# KeyBoard.net
KiCad netlist of a schematic drawn in EasyEDA Pro
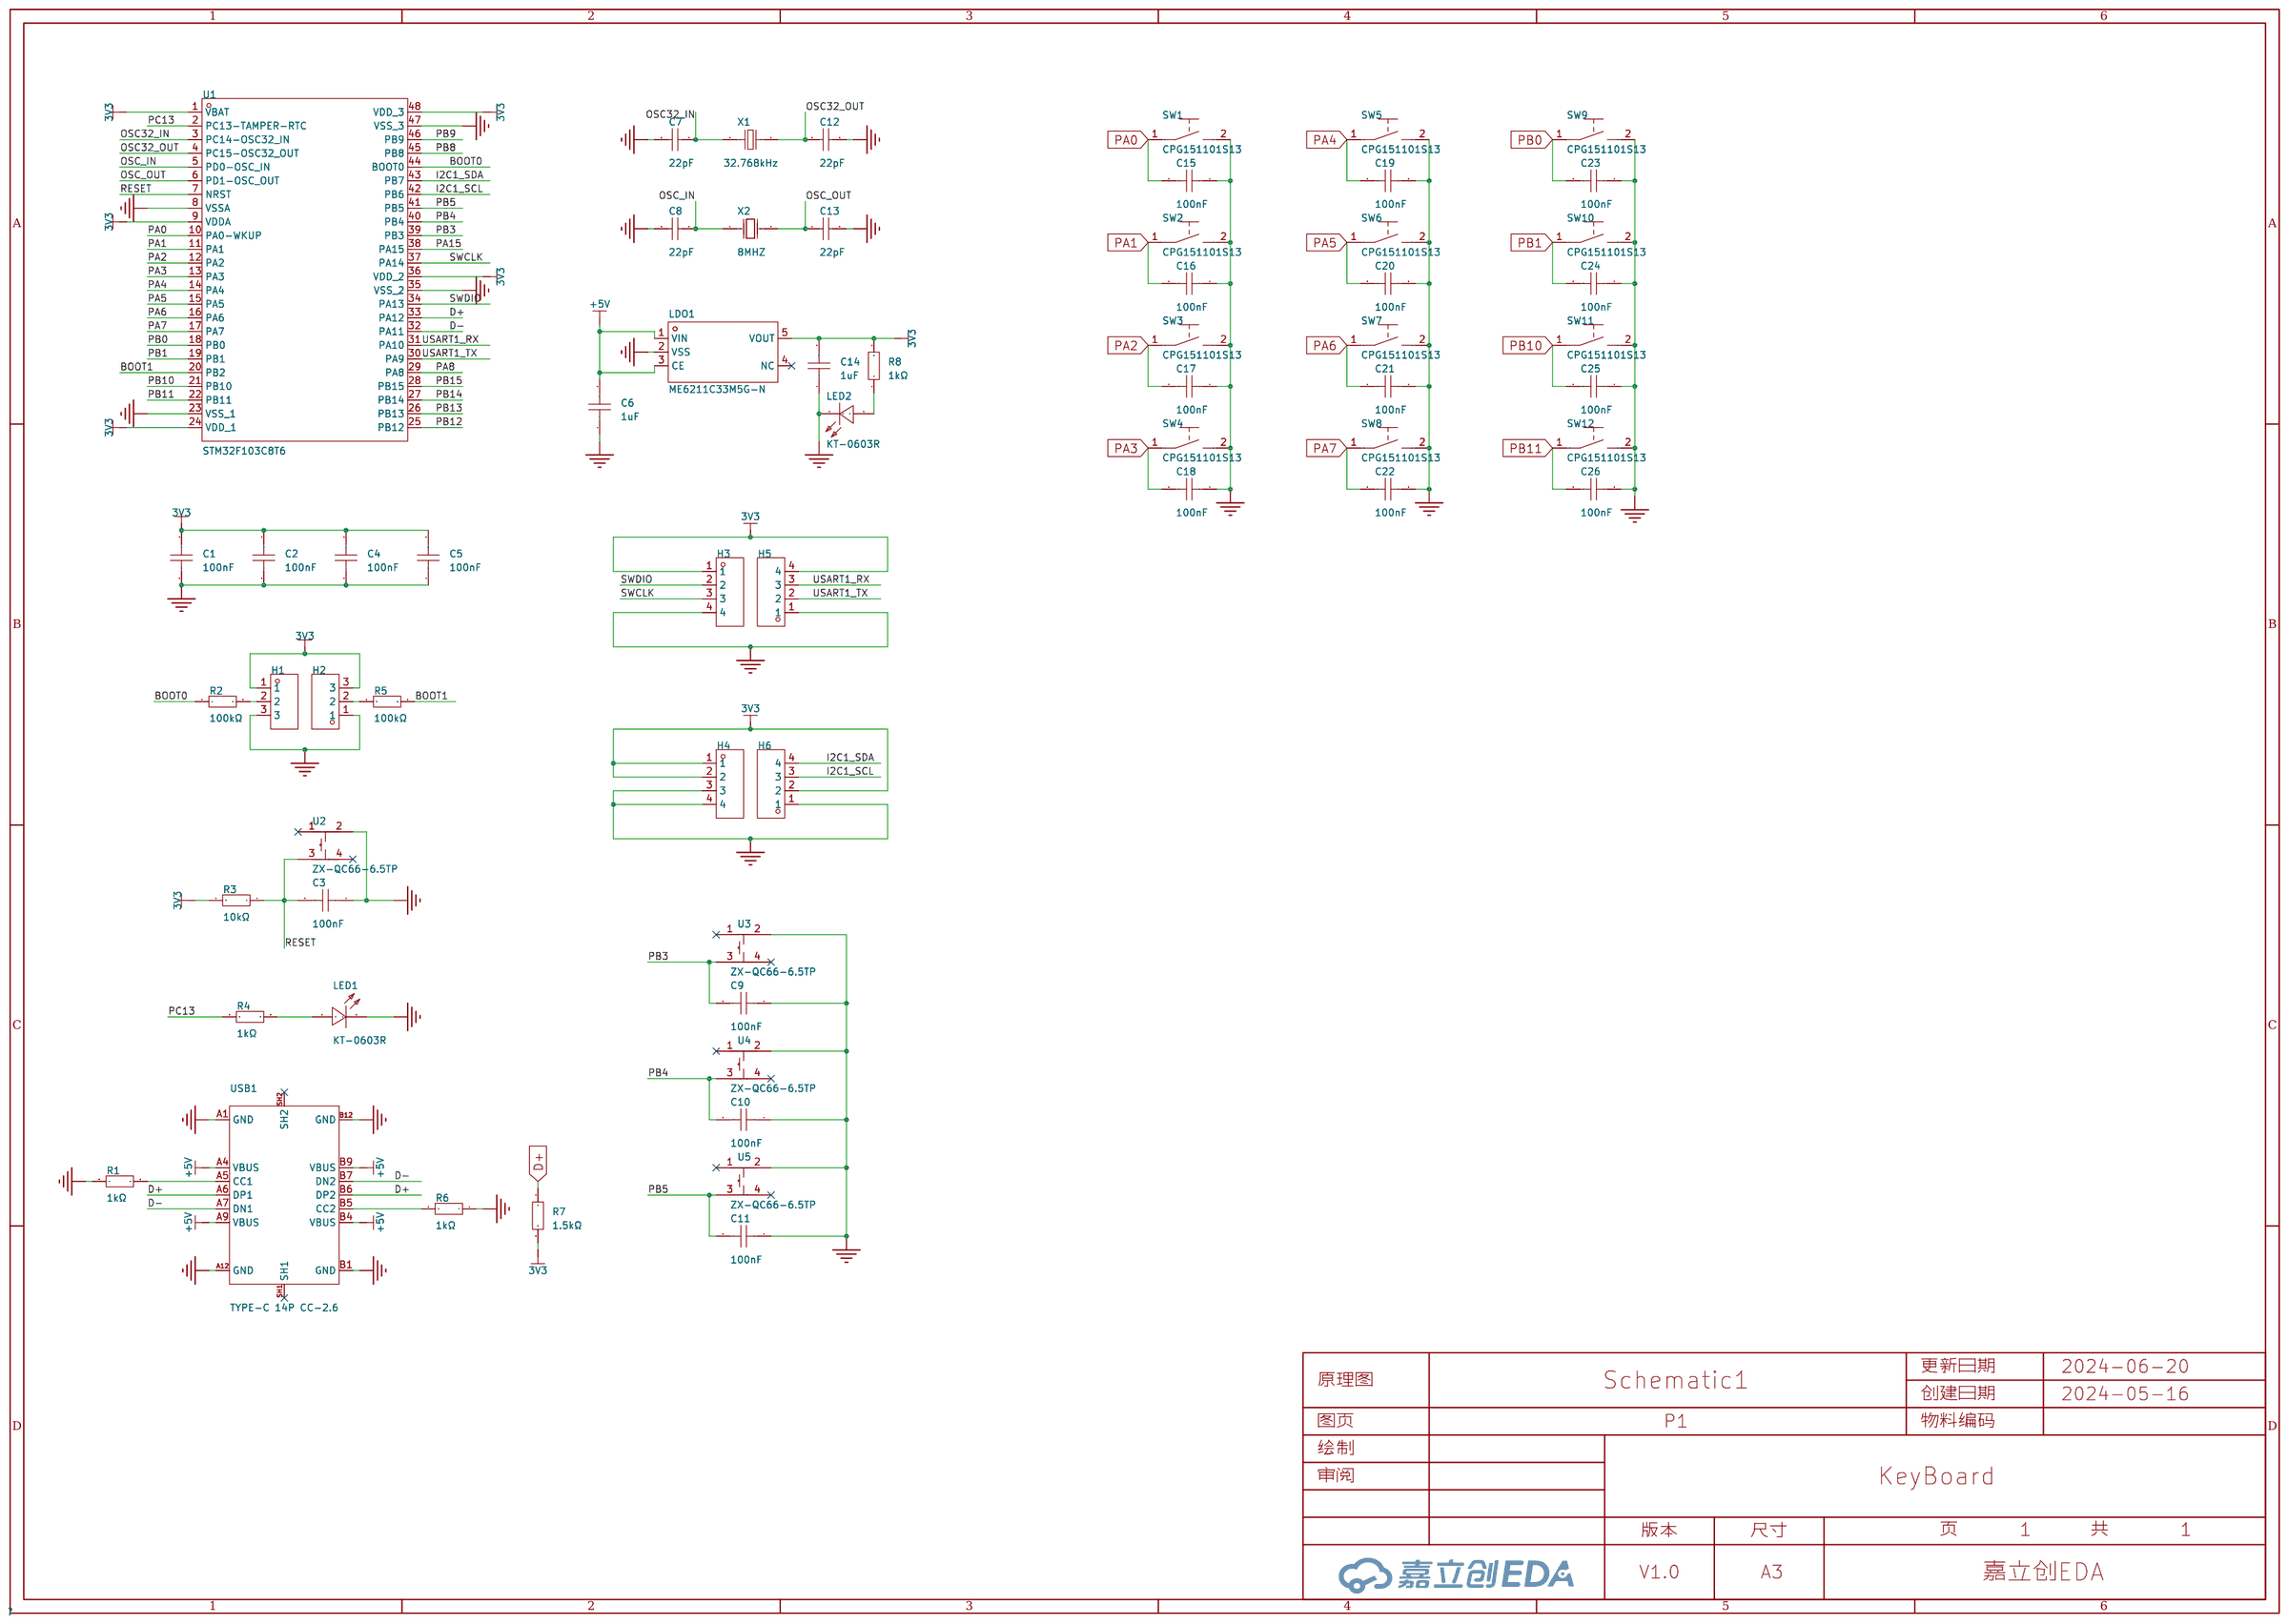
[diagram p0: schematic sheet]

(export (version "E")
  (design (tool "Eeschema 10.0.6"))
  (components
    (comp (ref "C1")
      (value "100nF")
      (footprint "easyedapro:C0603")
      (description "容值:100nF;精度:±10%;额定电压:50V;材质(温度系数):X7R;")
      (fields
        (field (name "Manufacturer Part") "CC0603KRX7R9BB104")
        (field (name "Manufacturer") "YAGEO(国巨)")
      )
      (libsource (lib "easyedapro") (part "CC0603KRX7R9BB104"))
    )
    (comp (ref "C2")
      (value "100nF")
      (footprint "easyedapro:C0603")
      (description "容值:100nF;精度:±10%;额定电压:50V;材质(温度系数):X7R;")
      (fields
        (field (name "Manufacturer Part") "CC0603KRX7R9BB104")
        (field (name "Manufacturer") "YAGEO(国巨)")
      )
      (libsource (lib "easyedapro") (part "CC0603KRX7R9BB104"))
    )
    (comp (ref "C3")
      (value "100nF")
      (footprint "easyedapro:C0603")
      (description "容值:100nF;精度:±10%;额定电压:50V;材质(温度系数):X7R;")
      (fields
        (field (name "Manufacturer Part") "CC0603KRX7R9BB104")
        (field (name "Manufacturer") "YAGEO(国巨)")
      )
      (libsource (lib "easyedapro") (part "CC0603KRX7R9BB104"))
    )
    (comp (ref "C4")
      (value "100nF")
      (footprint "easyedapro:C0603")
      (description "容值:100nF;精度:±10%;额定电压:50V;材质(温度系数):X7R;")
      (fields
        (field (name "Manufacturer Part") "CC0603KRX7R9BB104")
        (field (name "Manufacturer") "YAGEO(国巨)")
      )
      (libsource (lib "easyedapro") (part "CC0603KRX7R9BB104"))
    )
    (comp (ref "C5")
      (value "100nF")
      (footprint "easyedapro:C0603")
      (description "容值:100nF;精度:±10%;额定电压:50V;材质(温度系数):X7R;")
      (fields
        (field (name "Manufacturer Part") "CC0603KRX7R9BB104")
        (field (name "Manufacturer") "YAGEO(国巨)")
      )
      (libsource (lib "easyedapro") (part "CC0603KRX7R9BB104"))
    )
    (comp (ref "C6")
      (value "1uF")
      (footprint "easyedapro:C0603")
      (description "容值:1uF;精度:±10%;额定电压:50V;材质(温度系数):X5R;")
      (fields
        (field (name "Manufacturer Part") "CL10A105KB8NNNC")
        (field (name "Manufacturer") "SAMSUNG(三星)")
      )
      (libsource (lib "easyedapro") (part "CL10A105KB8NNNC"))
    )
    (comp (ref "C7")
      (value "22pF")
      (footprint "easyedapro:C0603")
      (description "容值:22pF;精度:±5%;额定电压:50V;材质(温度系数):C0G;")
      (fields
        (field (name "Manufacturer Part") "CL10C220JB8NNNC")
        (field (name "Manufacturer") "SAMSUNG(三星)")
      )
      (libsource (lib "easyedapro") (part "CL10C220JB8NNNC"))
    )
    (comp (ref "C8")
      (value "22pF")
      (footprint "easyedapro:C0603")
      (description "容值:22pF;精度:±5%;额定电压:50V;材质(温度系数):C0G;")
      (fields
        (field (name "Manufacturer Part") "CL10C220JB8NNNC")
        (field (name "Manufacturer") "SAMSUNG(三星)")
      )
      (libsource (lib "easyedapro") (part "CL10C220JB8NNNC"))
    )
    (comp (ref "C9")
      (value "100nF")
      (footprint "easyedapro:C0603")
      (description "容值:100nF;精度:±10%;额定电压:50V;材质(温度系数):X7R;")
      (fields
        (field (name "Manufacturer Part") "CC0603KRX7R9BB104")
        (field (name "Manufacturer") "YAGEO(国巨)")
      )
      (libsource (lib "easyedapro") (part "CC0603KRX7R9BB104"))
    )
    (comp (ref "C10")
      (value "100nF")
      (footprint "easyedapro:C0603")
      (description "容值:100nF;精度:±10%;额定电压:50V;材质(温度系数):X7R;")
      (fields
        (field (name "Manufacturer Part") "CC0603KRX7R9BB104")
        (field (name "Manufacturer") "YAGEO(国巨)")
      )
      (libsource (lib "easyedapro") (part "CC0603KRX7R9BB104"))
    )
    (comp (ref "C11")
      (value "100nF")
      (footprint "easyedapro:C0603")
      (description "容值:100nF;精度:±10%;额定电压:50V;材质(温度系数):X7R;")
      (fields
        (field (name "Manufacturer Part") "CC0603KRX7R9BB104")
        (field (name "Manufacturer") "YAGEO(国巨)")
      )
      (libsource (lib "easyedapro") (part "CC0603KRX7R9BB104"))
    )
    (comp (ref "C12")
      (value "22pF")
      (footprint "easyedapro:C0603")
      (description "容值:22pF;精度:±5%;额定电压:50V;材质(温度系数):C0G;")
      (fields
        (field (name "Manufacturer Part") "CL10C220JB8NNNC")
        (field (name "Manufacturer") "SAMSUNG(三星)")
      )
      (libsource (lib "easyedapro") (part "CL10C220JB8NNNC"))
    )
    (comp (ref "C13")
      (value "22pF")
      (footprint "easyedapro:C0603")
      (description "容值:22pF;精度:±5%;额定电压:50V;材质(温度系数):C0G;")
      (fields
        (field (name "Manufacturer Part") "CL10C220JB8NNNC")
        (field (name "Manufacturer") "SAMSUNG(三星)")
      )
      (libsource (lib "easyedapro") (part "CL10C220JB8NNNC"))
    )
    (comp (ref "C14")
      (value "1uF")
      (footprint "easyedapro:C0603")
      (description "容值:1uF;精度:±10%;额定电压:50V;材质(温度系数):X5R;")
      (fields
        (field (name "Manufacturer Part") "CL10A105KB8NNNC")
        (field (name "Manufacturer") "SAMSUNG(三星)")
      )
      (libsource (lib "easyedapro") (part "CL10A105KB8NNNC"))
    )
    (comp (ref "C15")
      (value "100nF")
      (footprint "easyedapro:C0603")
      (description "容值:100nF;精度:±10%;额定电压:50V;材质(温度系数):X7R;")
      (fields
        (field (name "Manufacturer Part") "CC0603KRX7R9BB104")
        (field (name "Manufacturer") "YAGEO(国巨)")
      )
      (libsource (lib "easyedapro") (part "CC0603KRX7R9BB104"))
    )
    (comp (ref "C16")
      (value "100nF")
      (footprint "easyedapro:C0603")
      (description "容值:100nF;精度:±10%;额定电压:50V;材质(温度系数):X7R;")
      (fields
        (field (name "Manufacturer Part") "CC0603KRX7R9BB104")
        (field (name "Manufacturer") "YAGEO(国巨)")
      )
      (libsource (lib "easyedapro") (part "CC0603KRX7R9BB104"))
    )
    (comp (ref "C17")
      (value "100nF")
      (footprint "easyedapro:C0603")
      (description "容值:100nF;精度:±10%;额定电压:50V;材质(温度系数):X7R;")
      (fields
        (field (name "Manufacturer Part") "CC0603KRX7R9BB104")
        (field (name "Manufacturer") "YAGEO(国巨)")
      )
      (libsource (lib "easyedapro") (part "CC0603KRX7R9BB104"))
    )
    (comp (ref "C18")
      (value "100nF")
      (footprint "easyedapro:C0603")
      (description "容值:100nF;精度:±10%;额定电压:50V;材质(温度系数):X7R;")
      (fields
        (field (name "Manufacturer Part") "CC0603KRX7R9BB104")
        (field (name "Manufacturer") "YAGEO(国巨)")
      )
      (libsource (lib "easyedapro") (part "CC0603KRX7R9BB104"))
    )
    (comp (ref "C19")
      (value "100nF")
      (footprint "easyedapro:C0603")
      (description "容值:100nF;精度:±10%;额定电压:50V;材质(温度系数):X7R;")
      (fields
        (field (name "Manufacturer Part") "CC0603KRX7R9BB104")
        (field (name "Manufacturer") "YAGEO(国巨)")
      )
      (libsource (lib "easyedapro") (part "CC0603KRX7R9BB104"))
    )
    (comp (ref "C20")
      (value "100nF")
      (footprint "easyedapro:C0603")
      (description "容值:100nF;精度:±10%;额定电压:50V;材质(温度系数):X7R;")
      (fields
        (field (name "Manufacturer Part") "CC0603KRX7R9BB104")
        (field (name "Manufacturer") "YAGEO(国巨)")
      )
      (libsource (lib "easyedapro") (part "CC0603KRX7R9BB104"))
    )
    (comp (ref "C21")
      (value "100nF")
      (footprint "easyedapro:C0603")
      (description "容值:100nF;精度:±10%;额定电压:50V;材质(温度系数):X7R;")
      (fields
        (field (name "Manufacturer Part") "CC0603KRX7R9BB104")
        (field (name "Manufacturer") "YAGEO(国巨)")
      )
      (libsource (lib "easyedapro") (part "CC0603KRX7R9BB104"))
    )
    (comp (ref "C22")
      (value "100nF")
      (footprint "easyedapro:C0603")
      (description "容值:100nF;精度:±10%;额定电压:50V;材质(温度系数):X7R;")
      (fields
        (field (name "Manufacturer Part") "CC0603KRX7R9BB104")
        (field (name "Manufacturer") "YAGEO(国巨)")
      )
      (libsource (lib "easyedapro") (part "CC0603KRX7R9BB104"))
    )
    (comp (ref "C23")
      (value "100nF")
      (footprint "easyedapro:C0603")
      (description "容值:100nF;精度:±10%;额定电压:50V;材质(温度系数):X7R;")
      (fields
        (field (name "Manufacturer Part") "CC0603KRX7R9BB104")
        (field (name "Manufacturer") "YAGEO(国巨)")
      )
      (libsource (lib "easyedapro") (part "CC0603KRX7R9BB104"))
    )
    (comp (ref "C24")
      (value "100nF")
      (footprint "easyedapro:C0603")
      (description "容值:100nF;精度:±10%;额定电压:50V;材质(温度系数):X7R;")
      (fields
        (field (name "Manufacturer Part") "CC0603KRX7R9BB104")
        (field (name "Manufacturer") "YAGEO(国巨)")
      )
      (libsource (lib "easyedapro") (part "CC0603KRX7R9BB104"))
    )
    (comp (ref "C25")
      (value "100nF")
      (footprint "easyedapro:C0603")
      (description "容值:100nF;精度:±10%;额定电压:50V;材质(温度系数):X7R;")
      (fields
        (field (name "Manufacturer Part") "CC0603KRX7R9BB104")
        (field (name "Manufacturer") "YAGEO(国巨)")
      )
      (libsource (lib "easyedapro") (part "CC0603KRX7R9BB104"))
    )
    (comp (ref "C26")
      (value "100nF")
      (footprint "easyedapro:C0603")
      (description "容值:100nF;精度:±10%;额定电压:50V;材质(温度系数):X7R;")
      (fields
        (field (name "Manufacturer Part") "CC0603KRX7R9BB104")
        (field (name "Manufacturer") "YAGEO(国巨)")
      )
      (libsource (lib "easyedapro") (part "CC0603KRX7R9BB104"))
    )
    (comp (ref "H1")
      (value "~")
      (footprint "easyedapro:HDR-TH_3P-P2.54-V-F")
      (libsource (lib "easyedapro") (part "PM254V-11-03-H85"))
    )
    (comp (ref "H2")
      (value "~")
      (footprint "easyedapro:HDR-TH_3P-P2.54-V-F")
      (libsource (lib "easyedapro") (part "PM254V-11-03-H85"))
    )
    (comp (ref "H3")
      (value "~")
      (footprint "easyedapro:HDR-TH_4P-P2.54-V-F")
      (libsource (lib "easyedapro") (part "2.54-1*4P母"))
    )
    (comp (ref "H4")
      (value "~")
      (footprint "easyedapro:HDR-TH_4P-P2.54-V-F")
      (libsource (lib "easyedapro") (part "2.54-1*4P母"))
    )
    (comp (ref "H5")
      (value "~")
      (footprint "easyedapro:HDR-TH_4P-P2.54-V-F")
      (libsource (lib "easyedapro") (part "2.54-1*4P母"))
    )
    (comp (ref "H6")
      (value "~")
      (footprint "easyedapro:HDR-TH_4P-P2.54-V-F")
      (libsource (lib "easyedapro") (part "2.54-1*4P母"))
    )
    (comp (ref "LDO1")
      (value "ME6211C33M5G-N")
      (footprint "easyedapro:SOT-23-5_L3.0-W1.7-P0.95-LS2.8-BL")
      (description "输出类型:固定;最大输入电压:6V;输出电压:3.3V;最大输出电流:500mA;电源纹波抑制比(PSRR):70dB;输出极性:正极;")
      (fields (field (name "Manufacturer") "MICRONE(南京微盟)"))
      (libsource (lib "easyedapro") (part "ME6211C33M5G-N"))
    )
    (comp (ref "LED1")
      (value "KT-0603R")
      (footprint "easyedapro:LED0603-RD")
      (description "发光颜色:红色;功率:-;正向电流:-;主波长:-;二极管配置:-;透镜颜色:-;色温:-;发光角度:-;载带方式:-;工作温度:-40°C~+85°C;")
      (fields (field (name "Manufacturer") "KENTO"))
      (libsource (lib "easyedapro") (part "KT-0603R"))
    )
    (comp (ref "LED2")
      (value "KT-0603R")
      (footprint "easyedapro:LED0603-RD")
      (description "发光颜色:红色;功率:-;正向电流:-;主波长:-;二极管配置:-;透镜颜色:-;色温:-;发光角度:-;载带方式:-;工作温度:-40°C~+85°C;")
      (fields (field (name "Manufacturer") "KENTO"))
      (libsource (lib "easyedapro") (part "KT-0603R"))
    )
    (comp (ref "R1")
      (value "1kΩ")
      (footprint "easyedapro:R0603")
      (description "电阻类型:厚膜电阻;阻值:10kΩ;精度:±1%;功率:100mW;最大工作电压:75V;温度系数:±100ppm/°C;")
      (fields
        (field (name "Manufacturer Part") "0603WAF1002T5E")
        (field (name "Manufacturer") "UNI-ROYAL(厚声)")
      )
      (libsource (lib "easyedapro") (part "0603WAF1002T5E"))
    )
    (comp (ref "R2")
      (value "100kΩ")
      (footprint "easyedapro:R0603")
      (description "电阻类型:厚膜电阻;阻值:100kΩ;精度:±1%;功率:100mW;最大工作电压:75V;温度系数:±100ppm/°C;")
      (fields
        (field (name "Manufacturer Part") "0603WAF1003T5E")
        (field (name "Manufacturer") "UNI-ROYAL(厚声)")
      )
      (libsource (lib "easyedapro") (part "0603WAF1003T5E"))
    )
    (comp (ref "R3")
      (value "10kΩ")
      (footprint "easyedapro:R0603")
      (description "电阻类型:厚膜电阻;阻值:10kΩ;精度:±1%;功率:100mW;最大工作电压:75V;温度系数:±100ppm/°C;")
      (fields
        (field (name "Manufacturer Part") "0603WAF1002T5E")
        (field (name "Manufacturer") "UNI-ROYAL(厚声)")
      )
      (libsource (lib "easyedapro") (part "0603WAF1002T5E"))
    )
    (comp (ref "R4")
      (value "1kΩ")
      (footprint "easyedapro:R0603")
      (description "电阻类型:厚膜电阻;阻值:1kΩ;精度:±1%;功率:100mW;最大工作电压:75V;温度系数:±100ppm/°C;")
      (fields
        (field (name "Manufacturer Part") "0603WAF1001T5E")
        (field (name "Manufacturer") "UNI-ROYAL(厚声)")
      )
      (libsource (lib "easyedapro") (part "0603WAF1001T5E"))
    )
    (comp (ref "R5")
      (value "100kΩ")
      (footprint "easyedapro:R0603")
      (description "电阻类型:厚膜电阻;阻值:100kΩ;精度:±1%;功率:100mW;最大工作电压:75V;温度系数:±100ppm/°C;")
      (fields
        (field (name "Manufacturer Part") "0603WAF1003T5E")
        (field (name "Manufacturer") "UNI-ROYAL(厚声)")
      )
      (libsource (lib "easyedapro") (part "0603WAF1003T5E"))
    )
    (comp (ref "R6")
      (value "1kΩ")
      (footprint "easyedapro:R0603")
      (description "电阻类型:厚膜电阻;阻值:10kΩ;精度:±1%;功率:100mW;最大工作电压:75V;温度系数:±100ppm/°C;")
      (fields
        (field (name "Manufacturer Part") "0603WAF1002T5E")
        (field (name "Manufacturer") "UNI-ROYAL(厚声)")
      )
      (libsource (lib "easyedapro") (part "0603WAF1002T5E"))
    )
    (comp (ref "R7")
      (value "1.5kΩ")
      (footprint "easyedapro:R0603")
      (description "电阻类型:厚膜电阻;阻值:1.5kΩ;精度:±1%;功率:100mW;最大工作电压:75V;温度系数:±100ppm/°C;")
      (fields
        (field (name "Manufacturer Part") "0603WAF1501T5E")
        (field (name "Manufacturer") "UNI-ROYAL(厚声)")
      )
      (libsource (lib "easyedapro") (part "0603WAF1501T5E"))
    )
    (comp (ref "R8")
      (value "1kΩ")
      (footprint "easyedapro:R0603")
      (description "电阻类型:厚膜电阻;阻值:1kΩ;精度:±1%;功率:100mW;最大工作电压:75V;温度系数:±100ppm/°C;")
      (fields
        (field (name "Manufacturer Part") "0603WAF1001T5E")
        (field (name "Manufacturer") "UNI-ROYAL(厚声)")
      )
      (libsource (lib "easyedapro") (part "0603WAF1001T5E"))
    )
    (comp (ref "SW1")
      (value "CPG151101S13")
      (footprint "easyedapro:KEY-TH_CPG1511F01S0X")
      (description "轴类型:青轴;工作电压:2V~12V;针脚数:2;操作力:50gf@±10gf;")
      (fields (field (name "Manufacturer") "Kailh(凯华)"))
      (libsource (lib "easyedapro") (part "CPG151101S13"))
    )
    (comp (ref "SW2")
      (value "CPG151101S13")
      (footprint "easyedapro:KEY-TH_CPG1511F01S0X")
      (description "轴类型:青轴;工作电压:2V~12V;针脚数:2;操作力:50gf@±10gf;")
      (fields (field (name "Manufacturer") "Kailh(凯华)"))
      (libsource (lib "easyedapro") (part "CPG151101S13"))
    )
    (comp (ref "SW3")
      (value "CPG151101S13")
      (footprint "easyedapro:KEY-TH_CPG1511F01S0X")
      (description "轴类型:青轴;工作电压:2V~12V;针脚数:2;操作力:50gf@±10gf;")
      (fields (field (name "Manufacturer") "Kailh(凯华)"))
      (libsource (lib "easyedapro") (part "CPG151101S13"))
    )
    (comp (ref "SW4")
      (value "CPG151101S13")
      (footprint "easyedapro:KEY-TH_CPG1511F01S0X")
      (description "轴类型:青轴;工作电压:2V~12V;针脚数:2;操作力:50gf@±10gf;")
      (fields (field (name "Manufacturer") "Kailh(凯华)"))
      (libsource (lib "easyedapro") (part "CPG151101S13"))
    )
    (comp (ref "SW5")
      (value "CPG151101S13")
      (footprint "easyedapro:KEY-TH_CPG1511F01S0X")
      (description "轴类型:青轴;工作电压:2V~12V;针脚数:2;操作力:50gf@±10gf;")
      (fields (field (name "Manufacturer") "Kailh(凯华)"))
      (libsource (lib "easyedapro") (part "CPG151101S13"))
    )
    (comp (ref "SW6")
      (value "CPG151101S13")
      (footprint "easyedapro:KEY-TH_CPG1511F01S0X")
      (description "轴类型:青轴;工作电压:2V~12V;针脚数:2;操作力:50gf@±10gf;")
      (fields (field (name "Manufacturer") "Kailh(凯华)"))
      (libsource (lib "easyedapro") (part "CPG151101S13"))
    )
    (comp (ref "SW7")
      (value "CPG151101S13")
      (footprint "easyedapro:KEY-TH_CPG1511F01S0X")
      (description "轴类型:青轴;工作电压:2V~12V;针脚数:2;操作力:50gf@±10gf;")
      (fields (field (name "Manufacturer") "Kailh(凯华)"))
      (libsource (lib "easyedapro") (part "CPG151101S13"))
    )
    (comp (ref "SW8")
      (value "CPG151101S13")
      (footprint "easyedapro:KEY-TH_CPG1511F01S0X")
      (description "轴类型:青轴;工作电压:2V~12V;针脚数:2;操作力:50gf@±10gf;")
      (fields (field (name "Manufacturer") "Kailh(凯华)"))
      (libsource (lib "easyedapro") (part "CPG151101S13"))
    )
    (comp (ref "SW9")
      (value "CPG151101S13")
      (footprint "easyedapro:KEY-TH_CPG1511F01S0X")
      (description "轴类型:青轴;工作电压:2V~12V;针脚数:2;操作力:50gf@±10gf;")
      (fields (field (name "Manufacturer") "Kailh(凯华)"))
      (libsource (lib "easyedapro") (part "CPG151101S13"))
    )
    (comp (ref "SW10")
      (value "CPG151101S13")
      (footprint "easyedapro:KEY-TH_CPG1511F01S0X")
      (description "轴类型:青轴;工作电压:2V~12V;针脚数:2;操作力:50gf@±10gf;")
      (fields (field (name "Manufacturer") "Kailh(凯华)"))
      (libsource (lib "easyedapro") (part "CPG151101S13"))
    )
    (comp (ref "SW11")
      (value "CPG151101S13")
      (footprint "easyedapro:KEY-TH_CPG1511F01S0X")
      (description "轴类型:青轴;工作电压:2V~12V;针脚数:2;操作力:50gf@±10gf;")
      (fields (field (name "Manufacturer") "Kailh(凯华)"))
      (libsource (lib "easyedapro") (part "CPG151101S13"))
    )
    (comp (ref "SW12")
      (value "CPG151101S13")
      (footprint "easyedapro:KEY-TH_CPG1511F01S0X")
      (description "轴类型:青轴;工作电压:2V~12V;针脚数:2;操作力:50gf@±10gf;")
      (fields (field (name "Manufacturer") "Kailh(凯华)"))
      (libsource (lib "easyedapro") (part "CPG151101S13"))
    )
    (comp (ref "U1")
      (value "STM32F103C8T6")
      (footprint "easyedapro:LQFP-48_L7.0-W7.0-P0.50-LS9.0-BL")
      (description "CPU内核:ARM-M3;程序存储容量:64KB;RAM总容量:20KB;GPIO端口数量:37;工作电压范围:2V~3.6V;CPU最大主频:72MHz;程序存储器类型:FLASH;")
      (fields (field (name "Manufacturer") "ST(意法半导体)"))
      (libsource (lib "easyedapro") (part "STM32F103C8T6"))
    )
    (comp (ref "U2")
      (value "ZX-QC66-6.5TP")
      (footprint "easyedapro:KEY-SMD_4P-L6.0-W6.0-P4.50-LS8.6")
      (fields (field (name "Manufacturer") "Megastar(兆星)"))
      (libsource (lib "easyedapro") (part "ZX-QC66-6.5TP"))
    )
    (comp (ref "U3")
      (value "ZX-QC66-6.5TP")
      (footprint "easyedapro:KEY-SMD_4P-L6.0-W6.0-P4.50-LS8.6")
      (fields (field (name "Manufacturer") "Megastar(兆星)"))
      (libsource (lib "easyedapro") (part "ZX-QC66-6.5TP"))
    )
    (comp (ref "U4")
      (value "ZX-QC66-6.5TP")
      (footprint "easyedapro:KEY-SMD_4P-L6.0-W6.0-P4.50-LS8.6")
      (fields (field (name "Manufacturer") "Megastar(兆星)"))
      (libsource (lib "easyedapro") (part "ZX-QC66-6.5TP"))
    )
    (comp (ref "U5")
      (value "ZX-QC66-6.5TP")
      (footprint "easyedapro:KEY-SMD_4P-L6.0-W6.0-P4.50-LS8.6")
      (fields (field (name "Manufacturer") "Megastar(兆星)"))
      (libsource (lib "easyedapro") (part "ZX-QC66-6.5TP"))
    )
    (comp (ref "USB1")
      (value "TYPE-C 14P CC-2.6")
      (footprint "easyedapro:TYPE-C-TH_TYPE-C-14P-CC-2.6")
      (description "连接器类型:Type-C;公母:母;端口数量:1;触点数量:14P;安装方式:侧插;额定电流 - 电源:3A;工作温度范围:-30°C~+85°C;")
      (fields (field (name "Manufacturer") "SHOU HAN(首韩)"))
      (libsource (lib "easyedapro") (part "TYPE-C 14P CC-2.6"))
    )
    (comp (ref "X1")
      (value "32.768kHz")
      (footprint "easyedapro:CRYSTAL-SMD_L3.2-W1.5-1")
      (description "晶振类型:贴片晶振;频率:32.768kHz;常温频差:±20ppm;外接负载电容:12.5pF;频率稳定度(全温):±20ppm;")
      (fields
        (field (name "Manufacturer Part") "FC31M2-32.768-NTLLLDT")
        (field (name "Manufacturer") "HCI(杭晶)")
      )
      (libsource (lib "easyedapro") (part "FC31M2-32.768-NTLLLDT"))
    )
    (comp (ref "X2")
      (value "8MHZ")
      (footprint "easyedapro:HC-49S_L11.5-W5.0-P4.88")
      (libsource (lib "easyedapro") (part "8MHZ_C9900021358"))
    )
  )
  (nets
    (net (code "1") (name "+5V") (class "Default")
      (node (ref "C6") (pin "2") (pinfunction "2_2") (pintype "unspecified"))
      (node (ref "LDO1") (pin "1") (pinfunction "VIN_1") (pintype "input"))
      (node (ref "LDO1") (pin "3") (pinfunction "CE_3") (pintype "input"))
      (node (ref "USB1") (pin "A4") (pinfunction "VBUS_A4") (pintype "unspecified"))
      (node (ref "USB1") (pin "A9") (pinfunction "VBUS_A9") (pintype "unspecified"))
      (node (ref "USB1") (pin "B4") (pinfunction "VBUS_B4") (pintype "unspecified"))
      (node (ref "USB1") (pin "B9") (pinfunction "VBUS_B9") (pintype "unspecified"))
    )
    (net (code "2") (name "/BOOT0") (class "Default")
      (node (ref "R2") (pin "1") (pinfunction "1_1") (pintype "input"))
      (node (ref "U1") (pin "44") (pinfunction "BOOT0_44") (pintype "unspecified"))
    )
    (net (code "3") (name "/BOOT1") (class "Default")
      (node (ref "R5") (pin "2") (pinfunction "2_2") (pintype "input"))
      (node (ref "U1") (pin "20") (pinfunction "PB2_20") (pintype "unspecified"))
    )
    (net (code "4") (name "/D-") (class "Default")
      (node (ref "U1") (pin "32") (pinfunction "PA11_32") (pintype "unspecified"))
      (node (ref "USB1") (pin "A7") (pinfunction "DN1_A7") (pintype "unspecified"))
      (node (ref "USB1") (pin "B7") (pinfunction "DN2_B7") (pintype "unspecified"))
    )
    (net (code "5") (name "/I2C1_SCL") (class "Default")
      (node (ref "H6") (pin "3") (pinfunction "3_3") (pintype "unspecified"))
      (node (ref "U1") (pin "42") (pinfunction "PB6_42") (pintype "unspecified"))
    )
    (net (code "6") (name "/I2C1_SDA") (class "Default")
      (node (ref "H6") (pin "4") (pinfunction "4_4") (pintype "unspecified"))
      (node (ref "U1") (pin "43") (pinfunction "PB7_43") (pintype "unspecified"))
    )
    (net (code "7") (name "/OSC32_IN") (class "Default")
      (node (ref "C7") (pin "2") (pinfunction "2_2") (pintype "input"))
      (node (ref "U1") (pin "3") (pinfunction "PC14-OSC32_IN_3") (pintype "unspecified"))
      (node (ref "X1") (pin "2") (pinfunction "2_2") (pintype "unspecified"))
    )
    (net (code "8") (name "/OSC32_OUT") (class "Default")
      (node (ref "C12") (pin "2") (pinfunction "2_2") (pintype "input"))
      (node (ref "U1") (pin "4") (pinfunction "PC15-OSC32_OUT_4") (pintype "unspecified"))
      (node (ref "X1") (pin "1") (pinfunction "1_1") (pintype "unspecified"))
    )
    (net (code "9") (name "/OSC_IN") (class "Default")
      (node (ref "C8") (pin "2") (pinfunction "2_2") (pintype "input"))
      (node (ref "U1") (pin "5") (pinfunction "PD0-OSC_IN_5") (pintype "unspecified"))
      (node (ref "X2") (pin "1") (pinfunction "OSC1_1") (pintype "input"))
    )
    (net (code "10") (name "/OSC_OUT") (class "Default")
      (node (ref "C13") (pin "1") (pinfunction "1_1") (pintype "input"))
      (node (ref "U1") (pin "6") (pinfunction "PD1-OSC_OUT_6") (pintype "unspecified"))
      (node (ref "X2") (pin "2") (pinfunction "OSC2_2") (pintype "input"))
    )
    (net (code "11") (name "/PA8") (class "Default")
      (node (ref "U1") (pin "29") (pinfunction "PA8_29") (pintype "unspecified"))
    )
    (net (code "12") (name "/PA15") (class "Default")
      (node (ref "U1") (pin "38") (pinfunction "PA15_38") (pintype "unspecified"))
    )
    (net (code "13") (name "/PB3") (class "Default")
      (node (ref "C9") (pin "2") (pinfunction "2_2") (pintype "unspecified"))
      (node (ref "U1") (pin "39") (pinfunction "PB3_39") (pintype "unspecified"))
      (node (ref "U3") (pin "3") (pinfunction "3_3") (pintype "unspecified"))
    )
    (net (code "14") (name "/PB4") (class "Default")
      (node (ref "C10") (pin "2") (pinfunction "2_2") (pintype "unspecified"))
      (node (ref "U1") (pin "40") (pinfunction "PB4_40") (pintype "unspecified"))
      (node (ref "U4") (pin "3") (pinfunction "3_3") (pintype "unspecified"))
    )
    (net (code "15") (name "/PB5") (class "Default")
      (node (ref "C11") (pin "2") (pinfunction "2_2") (pintype "unspecified"))
      (node (ref "U1") (pin "41") (pinfunction "PB5_41") (pintype "unspecified"))
      (node (ref "U5") (pin "3") (pinfunction "3_3") (pintype "unspecified"))
    )
    (net (code "16") (name "/PB8") (class "Default")
      (node (ref "U1") (pin "45") (pinfunction "PB8_45") (pintype "unspecified"))
    )
    (net (code "17") (name "/PB9") (class "Default")
      (node (ref "U1") (pin "46") (pinfunction "PB9_46") (pintype "unspecified"))
    )
    (net (code "18") (name "/PB12") (class "Default")
      (node (ref "U1") (pin "25") (pinfunction "PB12_25") (pintype "unspecified"))
    )
    (net (code "19") (name "/PB13") (class "Default")
      (node (ref "U1") (pin "26") (pinfunction "PB13_26") (pintype "unspecified"))
    )
    (net (code "20") (name "/PB14") (class "Default")
      (node (ref "U1") (pin "27") (pinfunction "PB14_27") (pintype "unspecified"))
    )
    (net (code "21") (name "/PB15") (class "Default")
      (node (ref "U1") (pin "28") (pinfunction "PB15_28") (pintype "unspecified"))
    )
    (net (code "22") (name "/PC13") (class "Default")
      (node (ref "R4") (pin "2") (pinfunction "2_2") (pintype "input"))
      (node (ref "U1") (pin "2") (pinfunction "PC13-TAMPER-RTC_2") (pintype "unspecified"))
    )
    (net (code "23") (name "/RESET") (class "Default")
      (node (ref "C3") (pin "2") (pinfunction "2_2") (pintype "unspecified"))
      (node (ref "R3") (pin "1") (pinfunction "1_1") (pintype "input"))
      (node (ref "U1") (pin "7") (pinfunction "NRST_7") (pintype "unspecified"))
      (node (ref "U2") (pin "3") (pinfunction "3_3") (pintype "unspecified"))
    )
    (net (code "24") (name "/SWCLK") (class "Default")
      (node (ref "H3") (pin "3") (pinfunction "3_3") (pintype "unspecified"))
      (node (ref "U1") (pin "37") (pinfunction "PA14_37") (pintype "unspecified"))
    )
    (net (code "25") (name "/SWDIO") (class "Default")
      (node (ref "H3") (pin "2") (pinfunction "2_2") (pintype "unspecified"))
      (node (ref "U1") (pin "34") (pinfunction "PA13_34") (pintype "unspecified"))
    )
    (net (code "26") (name "/USART1_RX") (class "Default")
      (node (ref "H5") (pin "3") (pinfunction "3_3") (pintype "unspecified"))
      (node (ref "U1") (pin "31") (pinfunction "PA10_31") (pintype "unspecified"))
    )
    (net (code "27") (name "/USART1_TX") (class "Default")
      (node (ref "H5") (pin "2") (pinfunction "2_2") (pintype "unspecified"))
      (node (ref "U1") (pin "30") (pinfunction "PA9_30") (pintype "unspecified"))
    )
    (net (code "28") (name "3V3") (class "Default")
      (node (ref "C1") (pin "2") (pinfunction "2_2") (pintype "unspecified"))
      (node (ref "C14") (pin "2") (pinfunction "2_2") (pintype "unspecified"))
      (node (ref "C2") (pin "2") (pinfunction "2_2") (pintype "unspecified"))
      (node (ref "C4") (pin "2") (pinfunction "2_2") (pintype "unspecified"))
      (node (ref "C5") (pin "2") (pinfunction "2_2") (pintype "unspecified"))
      (node (ref "H1") (pin "1") (pinfunction "1_1") (pintype "unspecified"))
      (node (ref "H2") (pin "3") (pinfunction "3_3") (pintype "unspecified"))
      (node (ref "H3") (pin "1") (pinfunction "1_1") (pintype "unspecified"))
      (node (ref "H4") (pin "1") (pinfunction "1_1") (pintype "unspecified"))
      (node (ref "H4") (pin "2") (pinfunction "2_2") (pintype "unspecified"))
      (node (ref "H5") (pin "4") (pinfunction "4_4") (pintype "unspecified"))
      (node (ref "H6") (pin "2") (pinfunction "2_2") (pintype "unspecified"))
      (node (ref "LDO1") (pin "5") (pinfunction "VOUT_5") (pintype "input"))
      (node (ref "R3") (pin "2") (pinfunction "2_2") (pintype "input"))
      (node (ref "R7") (pin "2") (pinfunction "2_2") (pintype "input"))
      (node (ref "R8") (pin "2") (pinfunction "2_2") (pintype "input"))
      (node (ref "U1") (pin "1") (pinfunction "VBAT_1") (pintype "unspecified"))
      (node (ref "U1") (pin "24") (pinfunction "VDD_1_24") (pintype "unspecified"))
      (node (ref "U1") (pin "36") (pinfunction "VDD_2_36") (pintype "unspecified"))
      (node (ref "U1") (pin "48") (pinfunction "VDD_3_48") (pintype "unspecified"))
      (node (ref "U1") (pin "9") (pinfunction "VDDA_9") (pintype "unspecified"))
    )
    (net (code "29") (name "D+") (class "Default")
      (node (ref "R7") (pin "1") (pinfunction "1_1") (pintype "input"))
      (node (ref "U1") (pin "33") (pinfunction "PA12_33") (pintype "unspecified"))
      (node (ref "USB1") (pin "A6") (pinfunction "DP1_A6") (pintype "unspecified"))
      (node (ref "USB1") (pin "B6") (pinfunction "DP2_B6") (pintype "unspecified"))
    )
    (net (code "30") (name "GND") (class "Default")
      (node (ref "C1") (pin "1") (pinfunction "1_1") (pintype "unspecified"))
      (node (ref "C10") (pin "1") (pinfunction "1_1") (pintype "unspecified"))
      (node (ref "C11") (pin "1") (pinfunction "1_1") (pintype "unspecified"))
      (node (ref "C12") (pin "1") (pinfunction "1_1") (pintype "input"))
      (node (ref "C13") (pin "2") (pinfunction "2_2") (pintype "input"))
      (node (ref "C14") (pin "1") (pinfunction "1_1") (pintype "unspecified"))
      (node (ref "C15") (pin "1") (pinfunction "1_1") (pintype "unspecified"))
      (node (ref "C16") (pin "1") (pinfunction "1_1") (pintype "unspecified"))
      (node (ref "C17") (pin "1") (pinfunction "1_1") (pintype "unspecified"))
      (node (ref "C18") (pin "1") (pinfunction "1_1") (pintype "unspecified"))
      (node (ref "C19") (pin "1") (pinfunction "1_1") (pintype "unspecified"))
      (node (ref "C2") (pin "1") (pinfunction "1_1") (pintype "unspecified"))
      (node (ref "C20") (pin "1") (pinfunction "1_1") (pintype "unspecified"))
      (node (ref "C21") (pin "1") (pinfunction "1_1") (pintype "unspecified"))
      (node (ref "C22") (pin "1") (pinfunction "1_1") (pintype "unspecified"))
      (node (ref "C23") (pin "1") (pinfunction "1_1") (pintype "unspecified"))
      (node (ref "C24") (pin "1") (pinfunction "1_1") (pintype "unspecified"))
      (node (ref "C25") (pin "1") (pinfunction "1_1") (pintype "unspecified"))
      (node (ref "C26") (pin "1") (pinfunction "1_1") (pintype "unspecified"))
      (node (ref "C3") (pin "1") (pinfunction "1_1") (pintype "unspecified"))
      (node (ref "C4") (pin "1") (pinfunction "1_1") (pintype "unspecified"))
      (node (ref "C5") (pin "1") (pinfunction "1_1") (pintype "unspecified"))
      (node (ref "C6") (pin "1") (pinfunction "1_1") (pintype "unspecified"))
      (node (ref "C7") (pin "1") (pinfunction "1_1") (pintype "input"))
      (node (ref "C8") (pin "1") (pinfunction "1_1") (pintype "input"))
      (node (ref "C9") (pin "1") (pinfunction "1_1") (pintype "unspecified"))
      (node (ref "H1") (pin "3") (pinfunction "3_3") (pintype "unspecified"))
      (node (ref "H2") (pin "1") (pinfunction "1_1") (pintype "unspecified"))
      (node (ref "H3") (pin "4") (pinfunction "4_4") (pintype "unspecified"))
      (node (ref "H4") (pin "3") (pinfunction "3_3") (pintype "unspecified"))
      (node (ref "H4") (pin "4") (pinfunction "4_4") (pintype "unspecified"))
      (node (ref "H5") (pin "1") (pinfunction "1_1") (pintype "unspecified"))
      (node (ref "H6") (pin "1") (pinfunction "1_1") (pintype "unspecified"))
      (node (ref "LDO1") (pin "2") (pinfunction "VSS_2") (pintype "input"))
      (node (ref "LED1") (pin "1") (pinfunction "K_1") (pintype "input"))
      (node (ref "LED2") (pin "1") (pinfunction "K_1") (pintype "input"))
      (node (ref "R1") (pin "2") (pinfunction "2_2") (pintype "input"))
      (node (ref "R6") (pin "1") (pinfunction "1_1") (pintype "input"))
      (node (ref "SW1") (pin "2") (pinfunction "2_2") (pintype "unspecified"))
      (node (ref "SW10") (pin "2") (pinfunction "2_2") (pintype "unspecified"))
      (node (ref "SW11") (pin "2") (pinfunction "2_2") (pintype "unspecified"))
      (node (ref "SW12") (pin "2") (pinfunction "2_2") (pintype "unspecified"))
      (node (ref "SW2") (pin "2") (pinfunction "2_2") (pintype "unspecified"))
      (node (ref "SW3") (pin "2") (pinfunction "2_2") (pintype "unspecified"))
      (node (ref "SW4") (pin "2") (pinfunction "2_2") (pintype "unspecified"))
      (node (ref "SW5") (pin "2") (pinfunction "2_2") (pintype "unspecified"))
      (node (ref "SW6") (pin "2") (pinfunction "2_2") (pintype "unspecified"))
      (node (ref "SW7") (pin "2") (pinfunction "2_2") (pintype "unspecified"))
      (node (ref "SW8") (pin "2") (pinfunction "2_2") (pintype "unspecified"))
      (node (ref "SW9") (pin "2") (pinfunction "2_2") (pintype "unspecified"))
      (node (ref "U1") (pin "23") (pinfunction "VSS_1_23") (pintype "unspecified"))
      (node (ref "U1") (pin "35") (pinfunction "VSS_2_35") (pintype "unspecified"))
      (node (ref "U1") (pin "47") (pinfunction "VSS_3_47") (pintype "unspecified"))
      (node (ref "U1") (pin "8") (pinfunction "VSSA_8") (pintype "unspecified"))
      (node (ref "U2") (pin "2") (pinfunction "2_2") (pintype "unspecified"))
      (node (ref "U3") (pin "2") (pinfunction "2_2") (pintype "unspecified"))
      (node (ref "U4") (pin "2") (pinfunction "2_2") (pintype "unspecified"))
      (node (ref "U5") (pin "2") (pinfunction "2_2") (pintype "unspecified"))
      (node (ref "USB1") (pin "A1") (pinfunction "GND_A1") (pintype "unspecified"))
      (node (ref "USB1") (pin "A12") (pinfunction "GND_A12") (pintype "unspecified"))
      (node (ref "USB1") (pin "B1") (pinfunction "GND_B1") (pintype "unspecified"))
      (node (ref "USB1") (pin "B12") (pinfunction "GND_B12") (pintype "unspecified"))
    )
    (net (code "31") (name "Net-(H1-Pad2)") (class "Default")
      (node (ref "H1") (pin "2") (pinfunction "2_2") (pintype "unspecified"))
      (node (ref "R2") (pin "2") (pinfunction "2_2") (pintype "input"))
    )
    (net (code "32") (name "Net-(H2-Pad2)") (class "Default")
      (node (ref "H2") (pin "2") (pinfunction "2_2") (pintype "unspecified"))
      (node (ref "R5") (pin "1") (pinfunction "1_1") (pintype "input"))
    )
    (net (code "33") (name "Net-(LED1-A)") (class "Default")
      (node (ref "LED1") (pin "2") (pinfunction "A_2") (pintype "input"))
      (node (ref "R4") (pin "1") (pinfunction "1_1") (pintype "input"))
    )
    (net (code "34") (name "Net-(LED2-A)") (class "Default")
      (node (ref "LED2") (pin "2") (pinfunction "A_2") (pintype "input"))
      (node (ref "R8") (pin "1") (pinfunction "1_1") (pintype "input"))
    )
    (net (code "35") (name "Net-(USB1-CC1)") (class "Default")
      (node (ref "R1") (pin "1") (pinfunction "1_1") (pintype "input"))
      (node (ref "USB1") (pin "A5") (pinfunction "CC1_A5") (pintype "unspecified"))
    )
    (net (code "36") (name "Net-(USB1-CC2)") (class "Default")
      (node (ref "R6") (pin "2") (pinfunction "2_2") (pintype "input"))
      (node (ref "USB1") (pin "B5") (pinfunction "CC2_B5") (pintype "unspecified"))
    )
    (net (code "37") (name "PA0") (class "Default")
      (node (ref "C15") (pin "2") (pinfunction "2_2") (pintype "unspecified"))
      (node (ref "SW1") (pin "1") (pinfunction "1_1") (pintype "unspecified"))
      (node (ref "U1") (pin "10") (pinfunction "PA0-WKUP_10") (pintype "unspecified"))
    )
    (net (code "38") (name "PA1") (class "Default")
      (node (ref "C16") (pin "2") (pinfunction "2_2") (pintype "unspecified"))
      (node (ref "SW2") (pin "1") (pinfunction "1_1") (pintype "unspecified"))
      (node (ref "U1") (pin "11") (pinfunction "PA1_11") (pintype "unspecified"))
    )
    (net (code "39") (name "PA2") (class "Default")
      (node (ref "C17") (pin "2") (pinfunction "2_2") (pintype "unspecified"))
      (node (ref "SW3") (pin "1") (pinfunction "1_1") (pintype "unspecified"))
      (node (ref "U1") (pin "12") (pinfunction "PA2_12") (pintype "unspecified"))
    )
    (net (code "40") (name "PA3") (class "Default")
      (node (ref "C18") (pin "2") (pinfunction "2_2") (pintype "unspecified"))
      (node (ref "SW4") (pin "1") (pinfunction "1_1") (pintype "unspecified"))
      (node (ref "U1") (pin "13") (pinfunction "PA3_13") (pintype "unspecified"))
    )
    (net (code "41") (name "PA4") (class "Default")
      (node (ref "C19") (pin "2") (pinfunction "2_2") (pintype "unspecified"))
      (node (ref "SW5") (pin "1") (pinfunction "1_1") (pintype "unspecified"))
      (node (ref "U1") (pin "14") (pinfunction "PA4_14") (pintype "unspecified"))
    )
    (net (code "42") (name "PA5") (class "Default")
      (node (ref "C20") (pin "2") (pinfunction "2_2") (pintype "unspecified"))
      (node (ref "SW6") (pin "1") (pinfunction "1_1") (pintype "unspecified"))
      (node (ref "U1") (pin "15") (pinfunction "PA5_15") (pintype "unspecified"))
    )
    (net (code "43") (name "PA6") (class "Default")
      (node (ref "C21") (pin "2") (pinfunction "2_2") (pintype "unspecified"))
      (node (ref "SW7") (pin "1") (pinfunction "1_1") (pintype "unspecified"))
      (node (ref "U1") (pin "16") (pinfunction "PA6_16") (pintype "unspecified"))
    )
    (net (code "44") (name "PA7") (class "Default")
      (node (ref "C22") (pin "2") (pinfunction "2_2") (pintype "unspecified"))
      (node (ref "SW8") (pin "1") (pinfunction "1_1") (pintype "unspecified"))
      (node (ref "U1") (pin "17") (pinfunction "PA7_17") (pintype "unspecified"))
    )
    (net (code "45") (name "PB0") (class "Default")
      (node (ref "C23") (pin "2") (pinfunction "2_2") (pintype "unspecified"))
      (node (ref "SW9") (pin "1") (pinfunction "1_1") (pintype "unspecified"))
      (node (ref "U1") (pin "18") (pinfunction "PB0_18") (pintype "unspecified"))
    )
    (net (code "46") (name "PB1") (class "Default")
      (node (ref "C24") (pin "2") (pinfunction "2_2") (pintype "unspecified"))
      (node (ref "SW10") (pin "1") (pinfunction "1_1") (pintype "unspecified"))
      (node (ref "U1") (pin "19") (pinfunction "PB1_19") (pintype "unspecified"))
    )
    (net (code "47") (name "PB10") (class "Default")
      (node (ref "C25") (pin "2") (pinfunction "2_2") (pintype "unspecified"))
      (node (ref "SW11") (pin "1") (pinfunction "1_1") (pintype "unspecified"))
      (node (ref "U1") (pin "21") (pinfunction "PB10_21") (pintype "unspecified"))
    )
    (net (code "48") (name "PB11") (class "Default")
      (node (ref "C26") (pin "2") (pinfunction "2_2") (pintype "unspecified"))
      (node (ref "SW12") (pin "1") (pinfunction "1_1") (pintype "unspecified"))
      (node (ref "U1") (pin "22") (pinfunction "PB11_22") (pintype "unspecified"))
    )
    (net (code "49") (name "unconnected-(LDO1-NC-Pad4)") (class "Default")
      (node (ref "LDO1") (pin "4") (pinfunction "NC_4") (pintype "input+no_connect"))
    )
    (net (code "50") (name "unconnected-(U2-Pad1)") (class "Default")
      (node (ref "U2") (pin "1") (pinfunction "1_1") (pintype "unspecified+no_connect"))
    )
    (net (code "51") (name "unconnected-(U2-Pad4)") (class "Default")
      (node (ref "U2") (pin "4") (pinfunction "4_4") (pintype "unspecified+no_connect"))
    )
    (net (code "52") (name "unconnected-(U3-Pad1)") (class "Default")
      (node (ref "U3") (pin "1") (pinfunction "1_1") (pintype "unspecified+no_connect"))
    )
    (net (code "53") (name "unconnected-(U3-Pad4)") (class "Default")
      (node (ref "U3") (pin "4") (pinfunction "4_4") (pintype "unspecified+no_connect"))
    )
    (net (code "54") (name "unconnected-(U4-Pad1)") (class "Default")
      (node (ref "U4") (pin "1") (pinfunction "1_1") (pintype "unspecified+no_connect"))
    )
    (net (code "55") (name "unconnected-(U4-Pad4)") (class "Default")
      (node (ref "U4") (pin "4") (pinfunction "4_4") (pintype "unspecified+no_connect"))
    )
    (net (code "56") (name "unconnected-(U5-Pad1)") (class "Default")
      (node (ref "U5") (pin "1") (pinfunction "1_1") (pintype "unspecified+no_connect"))
    )
    (net (code "57") (name "unconnected-(U5-Pad4)") (class "Default")
      (node (ref "U5") (pin "4") (pinfunction "4_4") (pintype "unspecified+no_connect"))
    )
    (net (code "58") (name "unconnected-(USB1-PadSH1)") (class "Default")
      (node (ref "USB1") (pin "SH1") (pinfunction "SH1_SH1") (pintype "unspecified+no_connect"))
    )
    (net (code "59") (name "unconnected-(USB1-PadSH2)") (class "Default")
      (node (ref "USB1") (pin "SH2") (pinfunction "SH2_SH2") (pintype "unspecified+no_connect"))
    )
  )
)
